# Polarshield_v2_0d.net
KiCad netlist of a schematic drawn in EAGLE
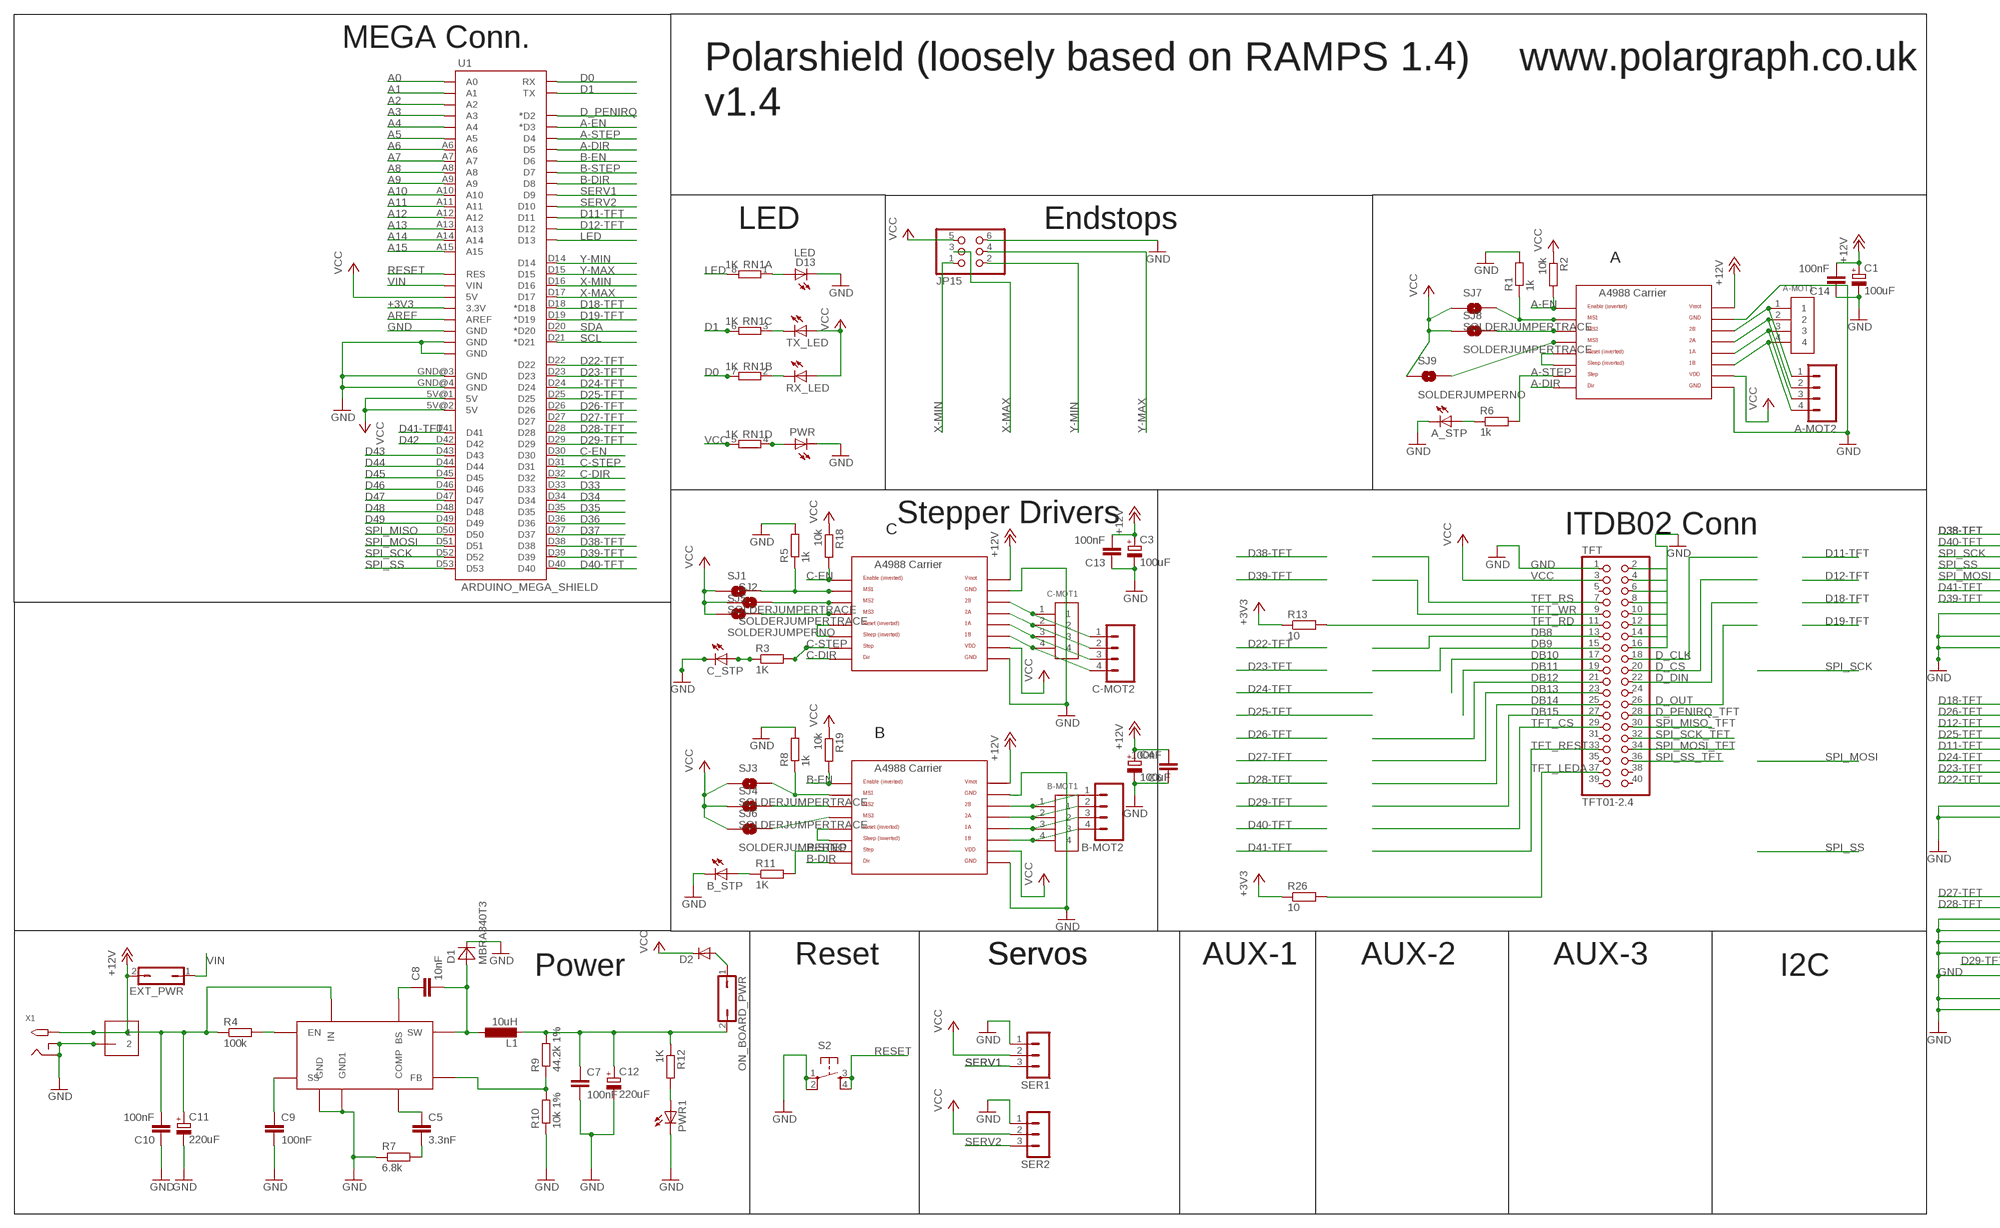
[diagram p0: schematic, sheet 1, part 1 of 2]
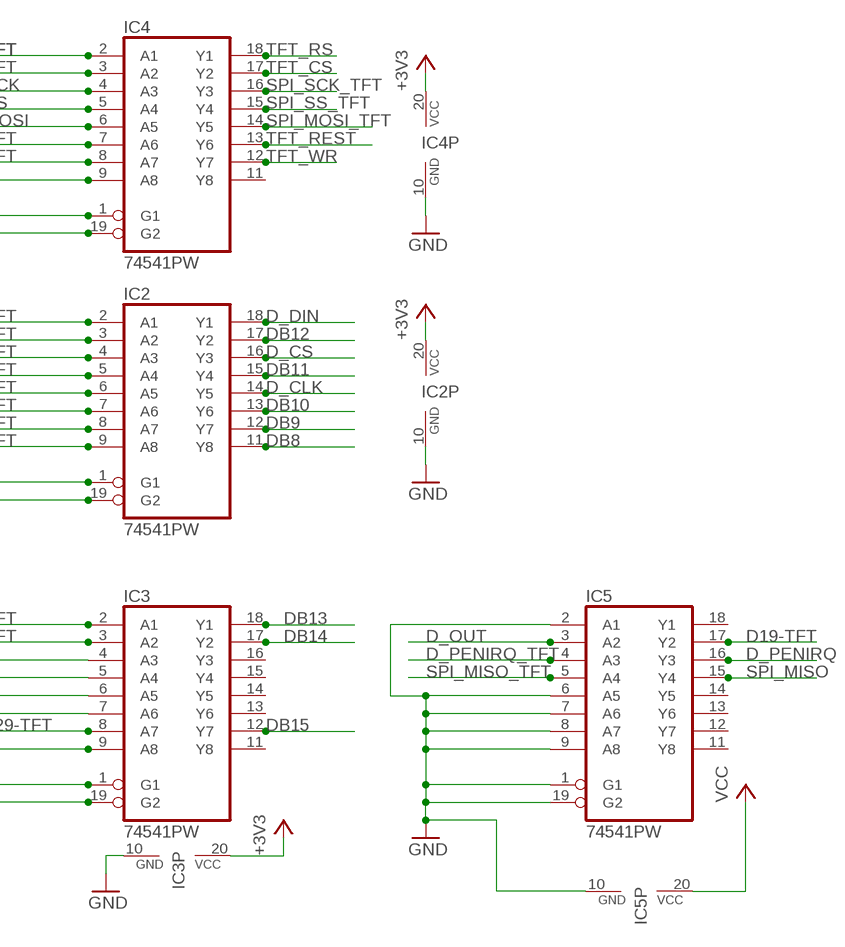
[diagram p1: schematic, sheet 1, part 2 of 2]

(export (version "E")
  (design (tool "Eeschema 10.0.6"))
  (components
    (comp (ref "A-MOT1")
      (value "1X4-BIG")
      (footprint "eagle-import:1X04-BIG")
      (libsource (lib "eagle-import") (part "1X4-BIG"))
    )
    (comp (ref "A-MOT2")
      (value "M04SCREW")
      (footprint "eagle-import:SCREWTERMINAL-3.5MM-4")
      (libsource (lib "eagle-import") (part "M04SCREW"))
    )
    (comp (ref "A_STP")
      (value "LEDCHIP-LED0805")
      (footprint "eagle-import:CHIP-LED0805")
      (libsource (lib "eagle-import") (part "LEDCHIP-LED0805"))
    )
    (comp (ref "B-MOT1")
      (value "1X4-BIG")
      (footprint "eagle-import:1X04-BIG")
      (libsource (lib "eagle-import") (part "1X4-BIG"))
    )
    (comp (ref "B-MOT2")
      (value "M04SCREW")
      (footprint "eagle-import:SCREWTERMINAL-3.5MM-4")
      (libsource (lib "eagle-import") (part "M04SCREW"))
    )
    (comp (ref "B_STP")
      (value "LEDCHIP-LED0805")
      (footprint "eagle-import:CHIP-LED0805")
      (libsource (lib "eagle-import") (part "LEDCHIP-LED0805"))
    )
    (comp (ref "C-MOT1")
      (value "1X4-BIG")
      (footprint "eagle-import:1X04-BIG")
      (libsource (lib "eagle-import") (part "1X4-BIG"))
    )
    (comp (ref "C-MOT2")
      (value "M04SCREW")
      (footprint "eagle-import:SCREWTERMINAL-3.5MM-4")
      (libsource (lib "eagle-import") (part "M04SCREW"))
    )
    (comp (ref "C1")
      (value "100uF")
      (footprint "eagle-import:153CLV-0605")
      (libsource (lib "eagle-import") (part "CPOL-EU153CLV-0605"))
    )
    (comp (ref "C3")
      (value "100uF")
      (footprint "eagle-import:153CLV-0605")
      (libsource (lib "eagle-import") (part "CPOL-EU153CLV-0605"))
    )
    (comp (ref "C4")
      (value "100uF")
      (footprint "eagle-import:153CLV-0605")
      (libsource (lib "eagle-import") (part "CPOL-EU153CLV-0605"))
    )
    (comp (ref "C5")
      (value "3.3nF")
      (footprint "eagle-import:C0805K")
      (libsource (lib "eagle-import") (part "C-EUC0805K"))
    )
    (comp (ref "C6")
      (value "100nF")
      (footprint "eagle-import:C0805")
      (libsource (lib "eagle-import") (part "C-EUC0805"))
    )
    (comp (ref "C7")
      (value "100nF")
      (footprint "eagle-import:C0805K")
      (libsource (lib "eagle-import") (part "C-EUC0805K"))
    )
    (comp (ref "C8")
      (value "10nF")
      (footprint "eagle-import:C0805K")
      (libsource (lib "eagle-import") (part "C-EUC0805K"))
    )
    (comp (ref "C9")
      (value "100nF")
      (footprint "eagle-import:C0805K")
      (libsource (lib "eagle-import") (part "C-EUC0805K"))
    )
    (comp (ref "C10")
      (value "100nF")
      (footprint "eagle-import:C0805K")
      (libsource (lib "eagle-import") (part "C-EUC0805K"))
    )
    (comp (ref "C11")
      (value "220uF")
      (footprint "eagle-import:153CLV-0807")
      (libsource (lib "eagle-import") (part "resistor_CPOL-EU153CLV-0807"))
    )
    (comp (ref "C12")
      (value "220uF")
      (footprint "eagle-import:153CLV-0807")
      (libsource (lib "eagle-import") (part "resistor_CPOL-EU153CLV-0807"))
    )
    (comp (ref "C13")
      (value "100nF")
      (footprint "eagle-import:C0805")
      (libsource (lib "eagle-import") (part "C-EUC0805"))
    )
    (comp (ref "C14")
      (value "100nF")
      (footprint "eagle-import:C0805")
      (libsource (lib "eagle-import") (part "C-EUC0805"))
    )
    (comp (ref "C_STP")
      (value "LEDCHIP-LED0805")
      (footprint "eagle-import:CHIP-LED0805")
      (libsource (lib "eagle-import") (part "LEDCHIP-LED0805"))
    )
    (comp (ref "D1")
      (value "MBRA340T3")
      (footprint "eagle-import:SMA")
      (libsource (lib "eagle-import") (part "MBRA340T3"))
    )
    (comp (ref "D2")
      (value "DIODE-DO214BA")
      (footprint "eagle-import:DO214BA")
      (libsource (lib "eagle-import") (part "DIODE-DO214BA"))
    )
    (comp (ref "D13")
      (value "LED")
      (footprint "eagle-import:CHIP-LED0805")
      (libsource (lib "eagle-import") (part "LEDCHIP-LED0805"))
    )
    (comp (ref "EXT_PWR")
      (value "JP1Q")
      (footprint "eagle-import:JP1")
      (libsource (lib "eagle-import") (part "JP1Q"))
    )
    (comp (ref "IC1")
      (value "MP2307")
      (footprint "eagle-import:SOIC8")
      (libsource (lib "eagle-import") (part "MP2307"))
    )
    (comp (ref "IC2")
      (value "74541PW")
      (footprint "eagle-import:TSSOP20")
      (libsource (lib "eagle-import") (part "74541PW"))
    )
    (comp (ref "IC3")
      (value "74541PW")
      (footprint "eagle-import:TSSOP20")
      (libsource (lib "eagle-import") (part "74541PW"))
    )
    (comp (ref "IC4")
      (value "74541PW")
      (footprint "eagle-import:TSSOP20")
      (libsource (lib "eagle-import") (part "74541PW"))
    )
    (comp (ref "IC5")
      (value "74541PW")
      (footprint "eagle-import:TSSOP20")
      (libsource (lib "eagle-import") (part "74541PW"))
    )
    (comp (ref "J1")
      (value "1X2-3.5MM")
      (footprint "eagle-import:1X2-3.5MM")
      (libsource (lib "eagle-import") (part "1X2-3.5MM"))
    )
    (comp (ref "JP15")
      (value "PINHD-2X3")
      (footprint "eagle-import:2X03")
      (libsource (lib "eagle-import") (part "PINHD-2X3"))
    )
    (comp (ref "L1")
      (value "10uH")
      (footprint "eagle-import:PIS2816")
      (libsource (lib "eagle-import") (part "L-EUPIS2816"))
    )
    (comp (ref "ON_BOARD_PWR")
      (value "JP1Q")
      (footprint "eagle-import:JP1")
      (libsource (lib "eagle-import") (part "JP1Q"))
    )
    (comp (ref "PWR")
      (value "LEDCHIP-LED0805")
      (footprint "eagle-import:CHIP-LED0805")
      (libsource (lib "eagle-import") (part "LEDCHIP-LED0805"))
    )
    (comp (ref "PWR1")
      (value "LEDCHIP-LED0805")
      (footprint "eagle-import:CHIP-LED0805")
      (libsource (lib "eagle-import") (part "LEDCHIP-LED0805"))
    )
    (comp (ref "R1")
      (value "1k")
      (footprint "eagle-import:R0805")
      (libsource (lib "eagle-import") (part "R-EU_R0805"))
    )
    (comp (ref "R2")
      (value "10k")
      (footprint "eagle-import:R0805")
      (libsource (lib "eagle-import") (part "R-EU_R0805"))
    )
    (comp (ref "R3")
      (value "1K")
      (footprint "eagle-import:R0805")
      (libsource (lib "eagle-import") (part "R-EU_R0805"))
    )
    (comp (ref "R4")
      (value "100k")
      (footprint "eagle-import:R0805")
      (libsource (lib "eagle-import") (part "resistor_R-EU_R0805"))
    )
    (comp (ref "R5")
      (value "1k")
      (footprint "eagle-import:R0805")
      (libsource (lib "eagle-import") (part "R-EU_R0805"))
    )
    (comp (ref "R6")
      (value "1k")
      (footprint "eagle-import:R0805")
      (libsource (lib "eagle-import") (part "R-EU_R0805"))
    )
    (comp (ref "R7")
      (value "6.8k")
      (footprint "eagle-import:R0805")
      (libsource (lib "eagle-import") (part "resistor_R-EU_R0805"))
    )
    (comp (ref "R8")
      (value "1k")
      (footprint "eagle-import:R0805")
      (libsource (lib "eagle-import") (part "R-EU_R0805"))
    )
    (comp (ref "R9")
      (value "44.2k 1%")
      (footprint "eagle-import:R0805")
      (libsource (lib "eagle-import") (part "resistor_R-EU_R0805"))
    )
    (comp (ref "R10")
      (value "10k 1%")
      (footprint "eagle-import:R0805")
      (libsource (lib "eagle-import") (part "resistor_R-EU_R0805"))
    )
    (comp (ref "R11")
      (value "1K")
      (footprint "eagle-import:R0805")
      (libsource (lib "eagle-import") (part "R-EU_R0805"))
    )
    (comp (ref "R12")
      (value "1K")
      (footprint "eagle-import:R0805")
      (libsource (lib "eagle-import") (part "R-EU_R0805"))
    )
    (comp (ref "R13")
      (value "10")
      (footprint "eagle-import:R0805")
      (libsource (lib "eagle-import") (part "resistor_R-EU_R0805"))
    )
    (comp (ref "R18")
      (value "10k")
      (footprint "eagle-import:R0805")
      (libsource (lib "eagle-import") (part "R-EU_R0805"))
    )
    (comp (ref "R19")
      (value "10k")
      (footprint "eagle-import:R0805")
      (libsource (lib "eagle-import") (part "R-EU_R0805"))
    )
    (comp (ref "R26")
      (value "10")
      (footprint "eagle-import:R0805")
      (libsource (lib "eagle-import") (part "resistor_R-EU_R0805"))
    )
    (comp (ref "RN1")
      (value "1K")
      (footprint "eagle-import:EXBS8V")
      (libsource (lib "eagle-import") (part "4R-NEXBS8V"))
    )
    (comp (ref "RX_LED")
      (value "LEDCHIP-LED0805")
      (footprint "eagle-import:CHIP-LED0805")
      (libsource (lib "eagle-import") (part "LEDCHIP-LED0805"))
    )
    (comp (ref "S2")
      (value "TAC_SWITCHPTH")
      (footprint "eagle-import:TACTILE-PTH")
      (libsource (lib "eagle-import") (part "TAC_SWITCHPTH"))
    )
    (comp (ref "SER1")
      (value "3PIN-HEADER")
      (footprint "eagle-import:3PIN-HEADER")
      (libsource (lib "eagle-import") (part "3PIN-HEADER"))
    )
    (comp (ref "SER2")
      (value "3PIN-HEADER")
      (footprint "eagle-import:3PIN-HEADER")
      (libsource (lib "eagle-import") (part "3PIN-HEADER"))
    )
    (comp (ref "SJ1")
      (value "SOLDERJUMPERTRACE")
      (footprint "eagle-import:SJ_2S-TRACE")
      (libsource (lib "eagle-import") (part "SOLDERJUMPERTRACE"))
    )
    (comp (ref "SJ2")
      (value "SOLDERJUMPERTRACE")
      (footprint "eagle-import:SJ_2S-TRACE")
      (libsource (lib "eagle-import") (part "SOLDERJUMPERTRACE"))
    )
    (comp (ref "SJ3")
      (value "SOLDERJUMPERTRACE")
      (footprint "eagle-import:SJ_2S-TRACE")
      (libsource (lib "eagle-import") (part "SOLDERJUMPERTRACE"))
    )
    (comp (ref "SJ4")
      (value "SOLDERJUMPERTRACE")
      (footprint "eagle-import:SJ_2S-TRACE")
      (libsource (lib "eagle-import") (part "SOLDERJUMPERTRACE"))
    )
    (comp (ref "SJ5")
      (value "SOLDERJUMPERNO")
      (footprint "eagle-import:SJ_2S-NO")
      (libsource (lib "eagle-import") (part "SOLDERJUMPERNO"))
    )
    (comp (ref "SJ6")
      (value "SOLDERJUMPERNO")
      (footprint "eagle-import:SJ_2S-NO")
      (libsource (lib "eagle-import") (part "SOLDERJUMPERNO"))
    )
    (comp (ref "SJ7")
      (value "SOLDERJUMPERTRACE")
      (footprint "eagle-import:SJ_2S-TRACE")
      (libsource (lib "eagle-import") (part "SOLDERJUMPERTRACE"))
    )
    (comp (ref "SJ8")
      (value "SOLDERJUMPERTRACE")
      (footprint "eagle-import:SJ_2S-TRACE")
      (libsource (lib "eagle-import") (part "SOLDERJUMPERTRACE"))
    )
    (comp (ref "SJ9")
      (value "SOLDERJUMPERNO")
      (footprint "eagle-import:SJ_2S-NO")
      (libsource (lib "eagle-import") (part "SOLDERJUMPERNO"))
    )
    (comp (ref "TFT")
      (value "TFT01-2.4")
      (footprint "eagle-import:TFT01-2.4")
      (libsource (lib "eagle-import") (part "TFT01-2.4"))
    )
    (comp (ref "TX_LED")
      (value "LEDCHIP-LED0805")
      (footprint "eagle-import:CHIP-LED0805")
      (libsource (lib "eagle-import") (part "LEDCHIP-LED0805"))
    )
    (comp (ref "U$1")
      (value "A4988BREAKOUT")
      (footprint "eagle-import:A4988BREAKOUT")
      (libsource (lib "eagle-import") (part "A4988BREAKOUT"))
    )
    (comp (ref "U$6")
      (value "A4988BREAKOUT")
      (footprint "eagle-import:A4988BREAKOUT")
      (libsource (lib "eagle-import") (part "A4988BREAKOUT"))
    )
    (comp (ref "U$7")
      (value "A4988BREAKOUT")
      (footprint "eagle-import:A4988BREAKOUT")
      (libsource (lib "eagle-import") (part "A4988BREAKOUT"))
    )
    (comp (ref "U1")
      (value "ARDUINO_MEGA_SHIELD")
      (footprint "eagle-import:ARDUINO_MEGA_SHIELD")
      (libsource (lib "eagle-import") (part "ARDUINO_MEGA_SHIELD"))
    )
    (comp (ref "X1")
      (value "2.1MMJACKTHM")
      (footprint "eagle-import:PJ-102A")
      (libsource (lib "eagle-import") (part "2.1MMJACKTHM"))
    )
  )
  (nets
    (net (code "1") (name "+3V3") (class "Default")
      (node (ref "IC2") (pin "20") (pinfunction "VCC_20") (pintype "power_in"))
      (node (ref "IC3") (pin "20") (pinfunction "VCC_20") (pintype "power_in"))
      (node (ref "IC4") (pin "20") (pinfunction "VCC_20") (pintype "power_in"))
      (node (ref "R13") (pin "1") (pinfunction "1_1") (pintype "passive"))
      (node (ref "R26") (pin "1") (pinfunction "1_1") (pintype "passive"))
      (node (ref "U1") (pin "3.3V") (pinfunction "3.3V_3.3V") (pintype "bidirectional"))
    )
    (net (code "2") (name "+12V") (class "Default")
      (node (ref "C1") (pin "+") (pinfunction "+_+") (pintype "passive"))
      (node (ref "C10") (pin "2") (pinfunction "2_2") (pintype "passive"))
      (node (ref "C11") (pin "+") (pinfunction "+_+") (pintype "passive"))
      (node (ref "C13") (pin "2") (pinfunction "2_2") (pintype "passive"))
      (node (ref "C14") (pin "2") (pinfunction "2_2") (pintype "passive"))
      (node (ref "C3") (pin "+") (pinfunction "+_+") (pintype "passive"))
      (node (ref "C4") (pin "+") (pinfunction "+_+") (pintype "passive"))
      (node (ref "C6") (pin "2") (pinfunction "2_2") (pintype "passive"))
      (node (ref "EXT_PWR") (pin "2") (pinfunction "2_2") (pintype "passive"))
      (node (ref "IC1") (pin "IN") (pinfunction "IN_IN") (pintype "bidirectional"))
      (node (ref "J1") (pin "1") (pinfunction "1_1") (pintype "passive"))
      (node (ref "R4") (pin "1") (pinfunction "1_1") (pintype "passive"))
      (node (ref "U$1") (pin "VMOT") (pinfunction "VMOT_VMOT") (pintype "power_in"))
      (node (ref "U$6") (pin "VMOT") (pinfunction "VMOT_VMOT") (pintype "power_in"))
      (node (ref "U$7") (pin "VMOT") (pinfunction "VMOT_VMOT") (pintype "power_in"))
      (node (ref "X1") (pin "TIP") (pinfunction "TIP_TIP") (pintype "bidirectional"))
    )
    (net (code "3") (name "/A-DIR") (class "Default")
      (node (ref "U$1") (pin "DIR") (pinfunction "DIR_DIR") (pintype "input"))
      (node (ref "U1") (pin "D5") (pinfunction "D5_D5") (pintype "bidirectional"))
    )
    (net (code "4") (name "/A-EN") (class "Default")
      (node (ref "R2") (pin "2") (pinfunction "2_2") (pintype "passive"))
      (node (ref "U$1") (pin "EN") (pinfunction "EN_EN") (pintype "input"))
      (node (ref "U1") (pin "D3") (pinfunction "*D3_D3") (pintype "bidirectional"))
    )
    (net (code "5") (name "/A-STEP") (class "Default")
      (node (ref "R6") (pin "2") (pinfunction "2_2") (pintype "passive"))
      (node (ref "U$1") (pin "STEP") (pinfunction "STEP_STEP") (pintype "input"))
      (node (ref "U1") (pin "D4") (pinfunction "D4_D4") (pintype "bidirectional"))
    )
    (net (code "6") (name "/A0") (class "Default")
      (node (ref "U1") (pin "A0") (pinfunction "A0_A0") (pintype "bidirectional"))
    )
    (net (code "7") (name "/A1") (class "Default")
      (node (ref "U1") (pin "A1") (pinfunction "A1_A1") (pintype "bidirectional"))
    )
    (net (code "8") (name "/A2") (class "Default")
      (node (ref "U1") (pin "A2") (pinfunction "A2_A2") (pintype "bidirectional"))
    )
    (net (code "9") (name "/A3") (class "Default")
      (node (ref "U1") (pin "A3") (pinfunction "A3_A3") (pintype "bidirectional"))
    )
    (net (code "10") (name "/A4") (class "Default")
      (node (ref "U1") (pin "A4") (pinfunction "A4_A4") (pintype "bidirectional"))
    )
    (net (code "11") (name "/A5") (class "Default")
      (node (ref "U1") (pin "A5") (pinfunction "A5_A5") (pintype "bidirectional"))
    )
    (net (code "12") (name "/A6") (class "Default")
      (node (ref "U1") (pin "A6") (pinfunction "A6_A6") (pintype "bidirectional"))
    )
    (net (code "13") (name "/A7") (class "Default")
      (node (ref "U1") (pin "A7") (pinfunction "A7_A7") (pintype "bidirectional"))
    )
    (net (code "14") (name "/A8") (class "Default")
      (node (ref "U1") (pin "A8") (pinfunction "A8_A8") (pintype "bidirectional"))
    )
    (net (code "15") (name "/A9") (class "Default")
      (node (ref "U1") (pin "A9") (pinfunction "A9_A9") (pintype "bidirectional"))
    )
    (net (code "16") (name "/A10") (class "Default")
      (node (ref "U1") (pin "A10") (pinfunction "A10_A10") (pintype "bidirectional"))
    )
    (net (code "17") (name "/A11") (class "Default")
      (node (ref "U1") (pin "A11") (pinfunction "A11_A11") (pintype "bidirectional"))
    )
    (net (code "18") (name "/A12") (class "Default")
      (node (ref "U1") (pin "A12") (pinfunction "A12_A12") (pintype "bidirectional"))
    )
    (net (code "19") (name "/A13") (class "Default")
      (node (ref "U1") (pin "A13") (pinfunction "A13_A13") (pintype "bidirectional"))
    )
    (net (code "20") (name "/A14") (class "Default")
      (node (ref "U1") (pin "A14") (pinfunction "A14_A14") (pintype "bidirectional"))
    )
    (net (code "21") (name "/A15") (class "Default")
      (node (ref "U1") (pin "A15") (pinfunction "A15_A15") (pintype "bidirectional"))
    )
    (net (code "22") (name "/AREF") (class "Default")
      (node (ref "U1") (pin "AREF") (pinfunction "AREF_AREF") (pintype "bidirectional"))
    )
    (net (code "23") (name "/B-DIR") (class "Default")
      (node (ref "U$7") (pin "DIR") (pinfunction "DIR_DIR") (pintype "input"))
      (node (ref "U1") (pin "D8") (pinfunction "D8_D8") (pintype "bidirectional"))
    )
    (net (code "24") (name "/B-EN") (class "Default")
      (node (ref "R19") (pin "2") (pinfunction "2_2") (pintype "passive"))
      (node (ref "U$7") (pin "EN") (pinfunction "EN_EN") (pintype "input"))
      (node (ref "U1") (pin "D6") (pinfunction "D6_D6") (pintype "bidirectional"))
    )
    (net (code "25") (name "/B-STEP") (class "Default")
      (node (ref "R11") (pin "2") (pinfunction "2_2") (pintype "passive"))
      (node (ref "U$7") (pin "STEP") (pinfunction "STEP_STEP") (pintype "input"))
      (node (ref "U1") (pin "D7") (pinfunction "D7_D7") (pintype "bidirectional"))
    )
    (net (code "26") (name "/C-DIR") (class "Default")
      (node (ref "U$6") (pin "DIR") (pinfunction "DIR_DIR") (pintype "input"))
      (node (ref "U1") (pin "D32") (pinfunction "D32_D32") (pintype "bidirectional"))
    )
    (net (code "27") (name "/C-EN") (class "Default")
      (node (ref "R18") (pin "2") (pinfunction "2_2") (pintype "passive"))
      (node (ref "U$6") (pin "EN") (pinfunction "EN_EN") (pintype "input"))
      (node (ref "U1") (pin "D30") (pinfunction "D30_D30") (pintype "bidirectional"))
    )
    (net (code "28") (name "/C-STEP") (class "Default")
      (node (ref "R3") (pin "2") (pinfunction "2_2") (pintype "passive"))
      (node (ref "U$6") (pin "STEP") (pinfunction "STEP_STEP") (pintype "input"))
      (node (ref "U1") (pin "D31") (pinfunction "D31_D31") (pintype "bidirectional"))
    )
    (net (code "29") (name "/D0") (class "Default")
      (node (ref "RN1") (pin "7") (pinfunction "2_7") (pintype "passive"))
      (node (ref "U1") (pin "RX") (pinfunction "RX_RX") (pintype "bidirectional"))
    )
    (net (code "30") (name "/D1") (class "Default")
      (node (ref "RN1") (pin "6") (pinfunction "2_6") (pintype "passive"))
      (node (ref "U1") (pin "TX") (pinfunction "TX_TX") (pintype "bidirectional"))
    )
    (net (code "31") (name "/D11-TFT") (class "Default")
      (node (ref "IC2") (pin "6") (pinfunction "A5_6") (pintype "input"))
      (node (ref "U1") (pin "D11") (pinfunction "D11_D11") (pintype "bidirectional"))
    )
    (net (code "32") (name "/D12-TFT") (class "Default")
      (node (ref "IC2") (pin "4") (pinfunction "A3_4") (pintype "input"))
      (node (ref "U1") (pin "D12") (pinfunction "D12_D12") (pintype "bidirectional"))
    )
    (net (code "33") (name "/D18-TFT") (class "Default")
      (node (ref "IC2") (pin "2") (pinfunction "A1_2") (pintype "input"))
      (node (ref "U1") (pin "D18") (pinfunction "*D18_D18") (pintype "bidirectional"))
    )
    (net (code "34") (name "/D19-TFT") (class "Default")
      (node (ref "IC5") (pin "17") (pinfunction "Y2_17") (pintype "tri_state"))
      (node (ref "U1") (pin "D19") (pinfunction "*D19_D19") (pintype "bidirectional"))
    )
    (net (code "35") (name "/D22-TFT") (class "Default")
      (node (ref "IC2") (pin "9") (pinfunction "A8_9") (pintype "input"))
      (node (ref "U1") (pin "D22") (pinfunction "D22_D22") (pintype "bidirectional"))
    )
    (net (code "36") (name "/D23-TFT") (class "Default")
      (node (ref "IC2") (pin "8") (pinfunction "A7_8") (pintype "input"))
      (node (ref "U1") (pin "D23") (pinfunction "D23_D23") (pintype "bidirectional"))
    )
    (net (code "37") (name "/D24-TFT") (class "Default")
      (node (ref "IC2") (pin "7") (pinfunction "A6_7") (pintype "input"))
      (node (ref "U1") (pin "D24") (pinfunction "D24_D24") (pintype "bidirectional"))
    )
    (net (code "38") (name "/D25-TFT") (class "Default")
      (node (ref "IC2") (pin "5") (pinfunction "A4_5") (pintype "input"))
      (node (ref "U1") (pin "D25") (pinfunction "D25_D25") (pintype "bidirectional"))
    )
    (net (code "39") (name "/D26-TFT") (class "Default")
      (node (ref "IC2") (pin "3") (pinfunction "A2_3") (pintype "input"))
      (node (ref "U1") (pin "D26") (pinfunction "D26_D26") (pintype "bidirectional"))
    )
    (net (code "40") (name "/D27-TFT") (class "Default")
      (node (ref "IC3") (pin "2") (pinfunction "A1_2") (pintype "input"))
      (node (ref "U1") (pin "D27") (pinfunction "D27_D27") (pintype "bidirectional"))
    )
    (net (code "41") (name "/D28-TFT") (class "Default")
      (node (ref "IC3") (pin "3") (pinfunction "A2_3") (pintype "input"))
      (node (ref "U1") (pin "D28") (pinfunction "D28_D28") (pintype "bidirectional"))
    )
    (net (code "42") (name "/D29-TFT") (class "Default")
      (node (ref "IC3") (pin "8") (pinfunction "A7_8") (pintype "input"))
      (node (ref "U1") (pin "D29") (pinfunction "D29_D29") (pintype "bidirectional"))
    )
    (net (code "43") (name "/D33") (class "Default")
      (node (ref "U1") (pin "D33") (pinfunction "D33_D33") (pintype "bidirectional"))
    )
    (net (code "44") (name "/D34") (class "Default")
      (node (ref "U1") (pin "D34") (pinfunction "D34_D34") (pintype "bidirectional"))
    )
    (net (code "45") (name "/D35") (class "Default")
      (node (ref "U1") (pin "D35") (pinfunction "D35_D35") (pintype "bidirectional"))
    )
    (net (code "46") (name "/D36") (class "Default")
      (node (ref "U1") (pin "D36") (pinfunction "D36_D36") (pintype "bidirectional"))
    )
    (net (code "47") (name "/D37") (class "Default")
      (node (ref "U1") (pin "D37") (pinfunction "D37_D37") (pintype "bidirectional"))
    )
    (net (code "48") (name "/D38-TFT") (class "Default")
      (node (ref "IC4") (pin "2") (pinfunction "A1_2") (pintype "input"))
      (node (ref "U1") (pin "D38") (pinfunction "D38_D38") (pintype "bidirectional"))
    )
    (net (code "49") (name "/D39-TFT") (class "Default")
      (node (ref "IC4") (pin "8") (pinfunction "A7_8") (pintype "input"))
      (node (ref "U1") (pin "D39") (pinfunction "D39_D39") (pintype "bidirectional"))
    )
    (net (code "50") (name "/D40-TFT") (class "Default")
      (node (ref "IC4") (pin "3") (pinfunction "A2_3") (pintype "input"))
      (node (ref "U1") (pin "D40") (pinfunction "D40_D40") (pintype "bidirectional"))
    )
    (net (code "51") (name "/D41-TFT") (class "Default")
      (node (ref "IC4") (pin "7") (pinfunction "A6_7") (pintype "input"))
      (node (ref "U1") (pin "D41") (pinfunction "D41_D41") (pintype "bidirectional"))
    )
    (net (code "52") (name "/D42") (class "Default")
      (node (ref "U1") (pin "D42") (pinfunction "D42_D42") (pintype "bidirectional"))
    )
    (net (code "53") (name "/D43") (class "Default")
      (node (ref "U1") (pin "D43") (pinfunction "D43_D43") (pintype "bidirectional"))
    )
    (net (code "54") (name "/D44") (class "Default")
      (node (ref "U1") (pin "D44") (pinfunction "D44_D44") (pintype "bidirectional"))
    )
    (net (code "55") (name "/D45") (class "Default")
      (node (ref "U1") (pin "D45") (pinfunction "D45_D45") (pintype "bidirectional"))
    )
    (net (code "56") (name "/D46") (class "Default")
      (node (ref "U1") (pin "D46") (pinfunction "D46_D46") (pintype "bidirectional"))
    )
    (net (code "57") (name "/D47") (class "Default")
      (node (ref "U1") (pin "D47") (pinfunction "D47_D47") (pintype "bidirectional"))
    )
    (net (code "58") (name "/D48") (class "Default")
      (node (ref "U1") (pin "D48") (pinfunction "D48_D48") (pintype "bidirectional"))
    )
    (net (code "59") (name "/D49") (class "Default")
      (node (ref "U1") (pin "D49") (pinfunction "D49_D49") (pintype "bidirectional"))
    )
    (net (code "60") (name "/DB8") (class "Default")
      (node (ref "IC2") (pin "11") (pinfunction "Y8_11") (pintype "tri_state"))
      (node (ref "TFT") (pin "13") (pinfunction "13_13") (pintype "passive"))
    )
    (net (code "61") (name "/DB9") (class "Default")
      (node (ref "IC2") (pin "12") (pinfunction "Y7_12") (pintype "tri_state"))
      (node (ref "TFT") (pin "15") (pinfunction "15_15") (pintype "passive"))
    )
    (net (code "62") (name "/DB10") (class "Default")
      (node (ref "IC2") (pin "13") (pinfunction "Y6_13") (pintype "tri_state"))
      (node (ref "TFT") (pin "17") (pinfunction "17_17") (pintype "passive"))
    )
    (net (code "63") (name "/DB11") (class "Default")
      (node (ref "IC2") (pin "15") (pinfunction "Y4_15") (pintype "tri_state"))
      (node (ref "TFT") (pin "19") (pinfunction "19_19") (pintype "passive"))
    )
    (net (code "64") (name "/DB12") (class "Default")
      (node (ref "IC2") (pin "17") (pinfunction "Y2_17") (pintype "tri_state"))
      (node (ref "TFT") (pin "21") (pinfunction "21_21") (pintype "passive"))
    )
    (net (code "65") (name "/DB13") (class "Default")
      (node (ref "IC3") (pin "18") (pinfunction "Y1_18") (pintype "tri_state"))
      (node (ref "TFT") (pin "23") (pinfunction "23_23") (pintype "passive"))
    )
    (net (code "66") (name "/DB14") (class "Default")
      (node (ref "IC3") (pin "17") (pinfunction "Y2_17") (pintype "tri_state"))
      (node (ref "TFT") (pin "25") (pinfunction "25_25") (pintype "passive"))
    )
    (net (code "67") (name "/DB15") (class "Default")
      (node (ref "IC3") (pin "12") (pinfunction "Y7_12") (pintype "tri_state"))
      (node (ref "TFT") (pin "27") (pinfunction "27_27") (pintype "passive"))
    )
    (net (code "68") (name "/D_CLK") (class "Default")
      (node (ref "IC2") (pin "14") (pinfunction "Y5_14") (pintype "tri_state"))
      (node (ref "TFT") (pin "18") (pinfunction "18_18") (pintype "passive"))
    )
    (net (code "69") (name "/D_CS") (class "Default")
      (node (ref "IC2") (pin "16") (pinfunction "Y3_16") (pintype "tri_state"))
      (node (ref "TFT") (pin "20") (pinfunction "20_20") (pintype "passive"))
    )
    (net (code "70") (name "/D_DIN") (class "Default")
      (node (ref "IC2") (pin "18") (pinfunction "Y1_18") (pintype "tri_state"))
      (node (ref "TFT") (pin "22") (pinfunction "22_22") (pintype "passive"))
    )
    (net (code "71") (name "/D_OUT") (class "Default")
      (node (ref "IC5") (pin "3") (pinfunction "A2_3") (pintype "input"))
      (node (ref "TFT") (pin "26") (pinfunction "26_26") (pintype "passive"))
    )
    (net (code "72") (name "/D_PENIRQ") (class "Default")
      (node (ref "IC5") (pin "16") (pinfunction "Y3_16") (pintype "tri_state"))
      (node (ref "U1") (pin "D2") (pinfunction "*D2_D2") (pintype "bidirectional"))
    )
    (net (code "73") (name "/D_PENIRQ_TFT") (class "Default")
      (node (ref "IC5") (pin "4") (pinfunction "A3_4") (pintype "input"))
      (node (ref "TFT") (pin "28") (pinfunction "28_28") (pintype "passive"))
    )
    (net (code "74") (name "/LED") (class "Default")
      (node (ref "RN1") (pin "8") (pinfunction "2_8") (pintype "passive"))
      (node (ref "U1") (pin "D13") (pinfunction "D13_D13") (pintype "bidirectional"))
    )
    (net (code "75") (name "/RESET") (class "Default")
      (node (ref "S2") (pin "3") (pinfunction "3_3") (pintype "passive"))
      (node (ref "S2") (pin "4") (pinfunction "4_4") (pintype "passive"))
      (node (ref "U1") (pin "RES") (pinfunction "RES_RES") (pintype "bidirectional"))
    )
    (net (code "76") (name "/SCL") (class "Default")
      (node (ref "U1") (pin "D21") (pinfunction "*D21_D21") (pintype "bidirectional"))
    )
    (net (code "77") (name "/SDA") (class "Default")
      (node (ref "U1") (pin "D20") (pinfunction "*D20_D20") (pintype "bidirectional"))
    )
    (net (code "78") (name "/SERV1") (class "Default")
      (node (ref "SER1") (pin "3") (pinfunction "3_3") (pintype "passive"))
      (node (ref "U1") (pin "D9") (pinfunction "D9_D9") (pintype "bidirectional"))
    )
    (net (code "79") (name "/SERV2") (class "Default")
      (node (ref "SER2") (pin "3") (pinfunction "3_3") (pintype "passive"))
      (node (ref "U1") (pin "D10") (pinfunction "D10_D10") (pintype "bidirectional"))
    )
    (net (code "80") (name "/SPI_MISO") (class "Default")
      (node (ref "IC5") (pin "15") (pinfunction "Y4_15") (pintype "tri_state"))
      (node (ref "U1") (pin "D50") (pinfunction "D50_D50") (pintype "bidirectional"))
    )
    (net (code "81") (name "/SPI_MISO_TFT") (class "Default")
      (node (ref "IC5") (pin "5") (pinfunction "A4_5") (pintype "input"))
      (node (ref "TFT") (pin "30") (pinfunction "30_30") (pintype "passive"))
    )
    (net (code "82") (name "/SPI_MOSI") (class "Default")
      (node (ref "IC4") (pin "6") (pinfunction "A5_6") (pintype "input"))
      (node (ref "U1") (pin "D51") (pinfunction "D51_D51") (pintype "bidirectional"))
    )
    (net (code "83") (name "/SPI_MOSI_TFT") (class "Default")
      (node (ref "IC4") (pin "14") (pinfunction "Y5_14") (pintype "tri_state"))
      (node (ref "TFT") (pin "34") (pinfunction "34_34") (pintype "passive"))
    )
    (net (code "84") (name "/SPI_SCK") (class "Default")
      (node (ref "IC4") (pin "4") (pinfunction "A3_4") (pintype "input"))
      (node (ref "U1") (pin "D52") (pinfunction "D52_D52") (pintype "bidirectional"))
    )
    (net (code "85") (name "/SPI_SCK_TFT") (class "Default")
      (node (ref "IC4") (pin "16") (pinfunction "Y3_16") (pintype "tri_state"))
      (node (ref "TFT") (pin "32") (pinfunction "32_32") (pintype "passive"))
    )
    (net (code "86") (name "/SPI_SS") (class "Default")
      (node (ref "IC4") (pin "5") (pinfunction "A4_5") (pintype "input"))
      (node (ref "U1") (pin "D53") (pinfunction "D53_D53") (pintype "bidirectional"))
    )
    (net (code "87") (name "/SPI_SS_TFT") (class "Default")
      (node (ref "IC4") (pin "15") (pinfunction "Y4_15") (pintype "tri_state"))
      (node (ref "TFT") (pin "36") (pinfunction "36_36") (pintype "passive"))
    )
    (net (code "88") (name "/TFT_CS") (class "Default")
      (node (ref "IC4") (pin "17") (pinfunction "Y2_17") (pintype "tri_state"))
      (node (ref "TFT") (pin "29") (pinfunction "29_29") (pintype "passive"))
    )
    (net (code "89") (name "/TFT_LEDA") (class "Default")
      (node (ref "R26") (pin "2") (pinfunction "2_2") (pintype "passive"))
      (node (ref "TFT") (pin "37") (pinfunction "37_37") (pintype "passive"))
    )
    (net (code "90") (name "/TFT_RD") (class "Default")
      (node (ref "R13") (pin "2") (pinfunction "2_2") (pintype "passive"))
      (node (ref "TFT") (pin "11") (pinfunction "11_11") (pintype "passive"))
    )
    (net (code "91") (name "/TFT_REST") (class "Default")
      (node (ref "IC4") (pin "13") (pinfunction "Y6_13") (pintype "tri_state"))
      (node (ref "TFT") (pin "33") (pinfunction "33_33") (pintype "passive"))
    )
    (net (code "92") (name "/TFT_RS") (class "Default")
      (node (ref "IC4") (pin "18") (pinfunction "Y1_18") (pintype "tri_state"))
      (node (ref "TFT") (pin "7") (pinfunction "7_7") (pintype "passive"))
    )
    (net (code "93") (name "/TFT_WR") (class "Default")
      (node (ref "IC4") (pin "12") (pinfunction "Y7_12") (pintype "tri_state"))
      (node (ref "TFT") (pin "9") (pinfunction "9_9") (pintype "passive"))
    )
    (net (code "94") (name "/VIN") (class "Default")
      (node (ref "EXT_PWR") (pin "1") (pinfunction "1_1") (pintype "passive"))
      (node (ref "U1") (pin "VIN") (pinfunction "VIN_VIN") (pintype "bidirectional"))
    )
    (net (code "95") (name "/X-MAX") (class "Default")
      (node (ref "JP15") (pin "3") (pinfunction "3_3") (pintype "passive"))
      (node (ref "U1") (pin "D17") (pinfunction "D17_D17") (pintype "bidirectional"))
    )
    (net (code "96") (name "/X-MIN") (class "Default")
      (node (ref "JP15") (pin "1") (pinfunction "1_1") (pintype "passive"))
      (node (ref "U1") (pin "D16") (pinfunction "D16_D16") (pintype "bidirectional"))
    )
    (net (code "97") (name "/Y-MAX") (class "Default")
      (node (ref "JP15") (pin "4") (pinfunction "4_4") (pintype "passive"))
      (node (ref "U1") (pin "D15") (pinfunction "D15_D15") (pintype "bidirectional"))
    )
    (net (code "98") (name "/Y-MIN") (class "Default")
      (node (ref "JP15") (pin "2") (pinfunction "2_2") (pintype "passive"))
      (node (ref "U1") (pin "D14") (pinfunction "D14_D14") (pintype "bidirectional"))
    )
    (net (code "99") (name "GND") (class "Default")
      (node (ref "A_STP") (pin "C") (pinfunction "C_C") (pintype "passive"))
      (node (ref "B_STP") (pin "C") (pinfunction "C_C") (pintype "passive"))
      (node (ref "C1") (pin "-") (pinfunction "-_-") (pintype "passive"))
      (node (ref "C10") (pin "1") (pinfunction "1_1") (pintype "passive"))
      (node (ref "C11") (pin "-") (pinfunction "-_-") (pintype "passive"))
      (node (ref "C12") (pin "-") (pinfunction "-_-") (pintype "passive"))
      (node (ref "C13") (pin "1") (pinfunction "1_1") (pintype "passive"))
      (node (ref "C14") (pin "1") (pinfunction "1_1") (pintype "passive"))
      (node (ref "C3") (pin "-") (pinfunction "-_-") (pintype "passive"))
      (node (ref "C4") (pin "-") (pinfunction "-_-") (pintype "passive"))
      (node (ref "C6") (pin "1") (pinfunction "1_1") (pintype "passive"))
      (node (ref "C7") (pin "2") (pinfunction "2_2") (pintype "passive"))
      (node (ref "C9") (pin "2") (pinfunction "2_2") (pintype "passive"))
      (node (ref "C_STP") (pin "C") (pinfunction "C_C") (pintype "passive"))
      (node (ref "D1") (pin "C") (pinfunction "C_C") (pintype "passive"))
      (node (ref "D13") (pin "C") (pinfunction "C_C") (pintype "passive"))
      (node (ref "IC1") (pin "GND") (pinfunction "GND_GND") (pintype "bidirectional"))
      (node (ref "IC1") (pin "GND1") (pinfunction "GND1_GND1") (pintype "bidirectional"))
      (node (ref "IC2") (pin "1") (pinfunction "G1_1") (pintype "input"))
      (node (ref "IC2") (pin "10") (pinfunction "GND_10") (pintype "power_in"))
      (node (ref "IC2") (pin "19") (pinfunction "G2_19") (pintype "input"))
      (node (ref "IC3") (pin "1") (pinfunction "G1_1") (pintype "input"))
      (node (ref "IC3") (pin "10") (pinfunction "GND_10") (pintype "power_in"))
      (node (ref "IC3") (pin "19") (pinfunction "G2_19") (pintype "input"))
      (node (ref "IC3") (pin "4") (pinfunction "A3_4") (pintype "input"))
      (node (ref "IC3") (pin "5") (pinfunction "A4_5") (pintype "input"))
      (node (ref "IC3") (pin "6") (pinfunction "A5_6") (pintype "input"))
      (node (ref "IC3") (pin "7") (pinfunction "A6_7") (pintype "input"))
      (node (ref "IC3") (pin "9") (pinfunction "A8_9") (pintype "input"))
      (node (ref "IC4") (pin "1") (pinfunction "G1_1") (pintype "input"))
      (node (ref "IC4") (pin "10") (pinfunction "GND_10") (pintype "power_in"))
      (node (ref "IC4") (pin "19") (pinfunction "G2_19") (pintype "input"))
      (node (ref "IC4") (pin "9") (pinfunction "A8_9") (pintype "input"))
      (node (ref "IC5") (pin "1") (pinfunction "G1_1") (pintype "input"))
      (node (ref "IC5") (pin "10") (pinfunction "GND_10") (pintype "power_in"))
      (node (ref "IC5") (pin "19") (pinfunction "G2_19") (pintype "input"))
      (node (ref "IC5") (pin "2") (pinfunction "A1_2") (pintype "input"))
      (node (ref "IC5") (pin "6") (pinfunction "A5_6") (pintype "input"))
      (node (ref "IC5") (pin "7") (pinfunction "A6_7") (pintype "input"))
      (node (ref "IC5") (pin "8") (pinfunction "A7_8") (pintype "input"))
      (node (ref "IC5") (pin "9") (pinfunction "A8_9") (pintype "input"))
      (node (ref "J1") (pin "2") (pinfunction "2_2") (pintype "passive"))
      (node (ref "JP15") (pin "6") (pinfunction "6_6") (pintype "passive"))
      (node (ref "PWR") (pin "C") (pinfunction "C_C") (pintype "passive"))
      (node (ref "PWR1") (pin "C") (pinfunction "C_C") (pintype "passive"))
      (node (ref "R1") (pin "2") (pinfunction "2_2") (pintype "passive"))
      (node (ref "R10") (pin "1") (pinfunction "1_1") (pintype "passive"))
      (node (ref "R5") (pin "2") (pinfunction "2_2") (pintype "passive"))
      (node (ref "R7") (pin "1") (pinfunction "1_1") (pintype "passive"))
      (node (ref "R8") (pin "2") (pinfunction "2_2") (pintype "passive"))
      (node (ref "S2") (pin "1") (pinfunction "1_1") (pintype "passive"))
      (node (ref "S2") (pin "2") (pinfunction "2_2") (pintype "passive"))
      (node (ref "SER1") (pin "1") (pinfunction "1_1") (pintype "passive"))
      (node (ref "SER2") (pin "1") (pinfunction "1_1") (pintype "passive"))
      (node (ref "TFT") (pin "1") (pinfunction "1_1") (pintype "passive"))
      (node (ref "TFT") (pin "10") (pinfunction "10_10") (pintype "passive"))
      (node (ref "TFT") (pin "12") (pinfunction "12_12") (pintype "passive"))
      (node (ref "TFT") (pin "14") (pinfunction "14_14") (pintype "passive"))
      (node (ref "TFT") (pin "16") (pinfunction "16_16") (pintype "passive"))
      (node (ref "TFT") (pin "2") (pinfunction "2_2") (pintype "passive"))
      (node (ref "TFT") (pin "4") (pinfunction "4_4") (pintype "passive"))
      (node (ref "TFT") (pin "6") (pinfunction "6_6") (pintype "passive"))
      (node (ref "TFT") (pin "8") (pinfunction "8_8") (pintype "passive"))
      (node (ref "U$1") (pin "GND") (pinfunction "GND_GND") (pintype "power_in"))
      (node (ref "U$1") (pin "GND@0") (pinfunction "GND_GND@0") (pintype "power_in"))
      (node (ref "U$6") (pin "GND") (pinfunction "GND_GND") (pintype "power_in"))
      (node (ref "U$6") (pin "GND@0") (pinfunction "GND_GND@0") (pintype "power_in"))
      (node (ref "U$7") (pin "GND") (pinfunction "GND_GND") (pintype "power_in"))
      (node (ref "U$7") (pin "GND@0") (pinfunction "GND_GND@0") (pintype "power_in"))
      (node (ref "U1") (pin "GND@0") (pinfunction "GND_GND@0") (pintype "power_in"))
      (node (ref "U1") (pin "GND@1") (pinfunction "GND_GND@1") (pintype "power_in"))
      (node (ref "U1") (pin "GND@2") (pinfunction "GND_GND@2") (pintype "power_in"))
      (node (ref "U1") (pin "GND@3") (pinfunction "GND_GND@3") (pintype "power_in"))
      (node (ref "U1") (pin "GND@4") (pinfunction "GND_GND@4") (pintype "power_in"))
      (node (ref "X1") (pin "RING") (pinfunction "RING_RING") (pintype "bidirectional"))
      (node (ref "X1") (pin "RING_SW") (pinfunction "RING_SW_RING_SW") (pintype "bidirectional"))
    )
    (net (code "100") (name "Net-(A-MOT1-Pad1)") (class "Default")
      (node (ref "A-MOT1") (pin "1") (pinfunction "1_1") (pintype "bidirectional"))
      (node (ref "A-MOT2") (pin "1") (pinfunction "1_1") (pintype "passive"))
      (node (ref "U$1") (pin "2B") (pinfunction "2B_2B") (pintype "output"))
    )
    (net (code "101") (name "Net-(A-MOT1-Pad2)") (class "Default")
      (node (ref "A-MOT1") (pin "2") (pinfunction "2_2") (pintype "bidirectional"))
      (node (ref "A-MOT2") (pin "2") (pinfunction "2_2") (pintype "passive"))
      (node (ref "U$1") (pin "2A") (pinfunction "2A_2A") (pintype "output"))
    )
    (net (code "102") (name "Net-(A-MOT1-Pad3)") (class "Default")
      (node (ref "A-MOT1") (pin "3") (pinfunction "3_3") (pintype "bidirectional"))
      (node (ref "A-MOT2") (pin "3") (pinfunction "3_3") (pintype "passive"))
      (node (ref "U$1") (pin "1A") (pinfunction "1A_1A") (pintype "output"))
    )
    (net (code "103") (name "Net-(A-MOT1-Pad4)") (class "Default")
      (node (ref "A-MOT1") (pin "4") (pinfunction "4_4") (pintype "bidirectional"))
      (node (ref "A-MOT2") (pin "4") (pinfunction "4_4") (pintype "passive"))
      (node (ref "U$1") (pin "1B") (pinfunction "1B_1B") (pintype "output"))
    )
    (net (code "104") (name "Net-(A_STP-PadA)") (class "Default")
      (node (ref "A_STP") (pin "A") (pinfunction "A_A") (pintype "passive"))
      (node (ref "R6") (pin "1") (pinfunction "1_1") (pintype "passive"))
    )
    (net (code "105") (name "Net-(B-MOT1-Pad1)") (class "Default")
      (node (ref "B-MOT1") (pin "1") (pinfunction "1_1") (pintype "bidirectional"))
      (node (ref "B-MOT2") (pin "1") (pinfunction "1_1") (pintype "passive"))
      (node (ref "U$7") (pin "2B") (pinfunction "2B_2B") (pintype "output"))
    )
    (net (code "106") (name "Net-(B-MOT1-Pad2)") (class "Default")
      (node (ref "B-MOT1") (pin "2") (pinfunction "2_2") (pintype "bidirectional"))
      (node (ref "B-MOT2") (pin "2") (pinfunction "2_2") (pintype "passive"))
      (node (ref "U$7") (pin "2A") (pinfunction "2A_2A") (pintype "output"))
    )
    (net (code "107") (name "Net-(B-MOT1-Pad3)") (class "Default")
      (node (ref "B-MOT1") (pin "3") (pinfunction "3_3") (pintype "bidirectional"))
      (node (ref "B-MOT2") (pin "3") (pinfunction "3_3") (pintype "passive"))
      (node (ref "U$7") (pin "1A") (pinfunction "1A_1A") (pintype "output"))
    )
    (net (code "108") (name "Net-(B-MOT1-Pad4)") (class "Default")
      (node (ref "B-MOT1") (pin "4") (pinfunction "4_4") (pintype "bidirectional"))
      (node (ref "B-MOT2") (pin "4") (pinfunction "4_4") (pintype "passive"))
      (node (ref "U$7") (pin "1B") (pinfunction "1B_1B") (pintype "output"))
    )
    (net (code "109") (name "Net-(B_STP-PadA)") (class "Default")
      (node (ref "B_STP") (pin "A") (pinfunction "A_A") (pintype "passive"))
      (node (ref "R11") (pin "1") (pinfunction "1_1") (pintype "passive"))
    )
    (net (code "110") (name "Net-(C-MOT1-Pad1)") (class "Default")
      (node (ref "C-MOT1") (pin "1") (pinfunction "1_1") (pintype "bidirectional"))
      (node (ref "C-MOT2") (pin "1") (pinfunction "1_1") (pintype "passive"))
      (node (ref "U$6") (pin "2B") (pinfunction "2B_2B") (pintype "output"))
    )
    (net (code "111") (name "Net-(C-MOT1-Pad2)") (class "Default")
      (node (ref "C-MOT1") (pin "2") (pinfunction "2_2") (pintype "bidirectional"))
      (node (ref "C-MOT2") (pin "2") (pinfunction "2_2") (pintype "passive"))
      (node (ref "U$6") (pin "2A") (pinfunction "2A_2A") (pintype "output"))
    )
    (net (code "112") (name "Net-(C-MOT1-Pad3)") (class "Default")
      (node (ref "C-MOT1") (pin "3") (pinfunction "3_3") (pintype "bidirectional"))
      (node (ref "C-MOT2") (pin "3") (pinfunction "3_3") (pintype "passive"))
      (node (ref "U$6") (pin "1A") (pinfunction "1A_1A") (pintype "output"))
    )
    (net (code "113") (name "Net-(C-MOT1-Pad4)") (class "Default")
      (node (ref "C-MOT1") (pin "4") (pinfunction "4_4") (pintype "bidirectional"))
      (node (ref "C-MOT2") (pin "4") (pinfunction "4_4") (pintype "passive"))
      (node (ref "U$6") (pin "1B") (pinfunction "1B_1B") (pintype "output"))
    )
    (net (code "114") (name "Net-(C5-Pad1)") (class "Default")
      (node (ref "C5") (pin "1") (pinfunction "1_1") (pintype "passive"))
      (node (ref "IC1") (pin "COMP") (pinfunction "COMP_COMP") (pintype "bidirectional"))
    )
    (net (code "115") (name "Net-(C5-Pad2)") (class "Default")
      (node (ref "C5") (pin "2") (pinfunction "2_2") (pintype "passive"))
      (node (ref "R7") (pin "2") (pinfunction "2_2") (pintype "passive"))
    )
    (net (code "116") (name "Net-(C8-Pad1)") (class "Default")
      (node (ref "C8") (pin "1") (pinfunction "1_1") (pintype "passive"))
      (node (ref "IC1") (pin "BS") (pinfunction "BS_BS") (pintype "bidirectional"))
    )
    (net (code "117") (name "Net-(C8-Pad2)") (class "Default")
      (node (ref "C8") (pin "2") (pinfunction "2_2") (pintype "passive"))
      (node (ref "D1") (pin "A") (pinfunction "A_A") (pintype "passive"))
      (node (ref "IC1") (pin "SW") (pinfunction "SW_SW") (pintype "bidirectional"))
      (node (ref "L1") (pin "1") (pinfunction "1_1") (pintype "passive"))
    )
    (net (code "118") (name "Net-(C9-Pad1)") (class "Default")
      (node (ref "C9") (pin "1") (pinfunction "1_1") (pintype "passive"))
      (node (ref "IC1") (pin "SS") (pinfunction "SS_SS") (pintype "bidirectional"))
    )
    (net (code "119") (name "Net-(C12-Pad+)") (class "Default")
      (node (ref "C12") (pin "+") (pinfunction "+_+") (pintype "passive"))
      (node (ref "C7") (pin "1") (pinfunction "1_1") (pintype "passive"))
      (node (ref "L1") (pin "2") (pinfunction "2_2") (pintype "passive"))
      (node (ref "ON_BOARD_PWR") (pin "2") (pinfunction "2_2") (pintype "passive"))
      (node (ref "R12") (pin "1") (pinfunction "1_1") (pintype "passive"))
      (node (ref "R9") (pin "2") (pinfunction "2_2") (pintype "passive"))
    )
    (net (code "120") (name "Net-(C_STP-PadA)") (class "Default")
      (node (ref "C_STP") (pin "A") (pinfunction "A_A") (pintype "passive"))
      (node (ref "R3") (pin "1") (pinfunction "1_1") (pintype "passive"))
    )
    (net (code "121") (name "Net-(D2-PadA)") (class "Default")
      (node (ref "D2") (pin "A") (pinfunction "A_A") (pintype "passive"))
      (node (ref "ON_BOARD_PWR") (pin "1") (pinfunction "1_1") (pintype "passive"))
    )
    (net (code "122") (name "Net-(D13-PadA)") (class "Default")
      (node (ref "D13") (pin "A") (pinfunction "A_A") (pintype "passive"))
      (node (ref "RN1") (pin "1") (pinfunction "1_1") (pintype "passive"))
    )
    (net (code "123") (name "Net-(IC1-PadEN)") (class "Default")
      (node (ref "IC1") (pin "EN") (pinfunction "EN_EN") (pintype "bidirectional"))
      (node (ref "R4") (pin "2") (pinfunction "2_2") (pintype "passive"))
    )
    (net (code "124") (name "Net-(IC1-PadFB)") (class "Default")
      (node (ref "IC1") (pin "FB") (pinfunction "FB_FB") (pintype "bidirectional"))
      (node (ref "R10") (pin "2") (pinfunction "2_2") (pintype "passive"))
      (node (ref "R9") (pin "1") (pinfunction "1_1") (pintype "passive"))
    )
    (net (code "125") (name "Net-(PWR1-PadA)") (class "Default")
      (node (ref "PWR1") (pin "A") (pinfunction "A_A") (pintype "passive"))
      (node (ref "R12") (pin "2") (pinfunction "2_2") (pintype "passive"))
    )
    (net (code "126") (name "Net-(R1-Pad1)") (class "Default")
      (node (ref "R1") (pin "1") (pinfunction "1_1") (pintype "passive"))
      (node (ref "SJ7") (pin "2") (pinfunction "2_2") (pintype "passive"))
      (node (ref "U$1") (pin "MS1") (pinfunction "MS1_MS1") (pintype "input"))
    )
    (net (code "127") (name "Net-(R5-Pad1)") (class "Default")
      (node (ref "R5") (pin "1") (pinfunction "1_1") (pintype "passive"))
      (node (ref "SJ1") (pin "2") (pinfunction "2_2") (pintype "passive"))
      (node (ref "U$6") (pin "MS1") (pinfunction "MS1_MS1") (pintype "input"))
    )
    (net (code "128") (name "Net-(R8-Pad1)") (class "Default")
      (node (ref "R8") (pin "1") (pinfunction "1_1") (pintype "passive"))
      (node (ref "SJ3") (pin "2") (pinfunction "2_2") (pintype "passive"))
      (node (ref "U$7") (pin "MS1") (pinfunction "MS1_MS1") (pintype "input"))
    )
    (net (code "129") (name "Net-(RN1B-1)") (class "Default")
      (node (ref "RN1") (pin "2") (pinfunction "1_2") (pintype "passive"))
      (node (ref "RX_LED") (pin "C") (pinfunction "C_C") (pintype "passive"))
    )
    (net (code "130") (name "Net-(RN1C-1)") (class "Default")
      (node (ref "RN1") (pin "3") (pinfunction "1_3") (pintype "passive"))
      (node (ref "TX_LED") (pin "C") (pinfunction "C_C") (pintype "passive"))
    )
    (net (code "131") (name "Net-(RN1D-1)") (class "Default")
      (node (ref "PWR") (pin "A") (pinfunction "A_A") (pintype "passive"))
      (node (ref "RN1") (pin "4") (pinfunction "1_4") (pintype "passive"))
    )
    (net (code "132") (name "Net-(SJ2-Pad2)") (class "Default")
      (node (ref "SJ2") (pin "2") (pinfunction "2_2") (pintype "passive"))
      (node (ref "U$6") (pin "MS2") (pinfunction "MS2_MS2") (pintype "input"))
    )
    (net (code "133") (name "Net-(SJ4-Pad2)") (class "Default")
      (node (ref "SJ4") (pin "2") (pinfunction "2_2") (pintype "passive"))
      (node (ref "U$7") (pin "MS2") (pinfunction "MS2_MS2") (pintype "input"))
    )
    (net (code "134") (name "Net-(SJ5-Pad2)") (class "Default")
      (node (ref "SJ5") (pin "2") (pinfunction "2_2") (pintype "passive"))
      (node (ref "U$6") (pin "MS3") (pinfunction "MS3_MS3") (pintype "input"))
    )
    (net (code "135") (name "Net-(SJ6-Pad2)") (class "Default")
      (node (ref "SJ6") (pin "2") (pinfunction "2_2") (pintype "passive"))
      (node (ref "U$7") (pin "MS3") (pinfunction "MS3_MS3") (pintype "input"))
    )
    (net (code "136") (name "Net-(SJ8-Pad2)") (class "Default")
      (node (ref "SJ8") (pin "2") (pinfunction "2_2") (pintype "passive"))
      (node (ref "U$1") (pin "MS2") (pinfunction "MS2_MS2") (pintype "input"))
    )
    (net (code "137") (name "Net-(SJ9-Pad2)") (class "Default")
      (node (ref "SJ9") (pin "2") (pinfunction "2_2") (pintype "passive"))
      (node (ref "U$1") (pin "MS3") (pinfunction "MS3_MS3") (pintype "input"))
    )
    (net (code "138") (name "Net-(U$1-SLEEP)") (class "Default")
      (node (ref "U$1") (pin "RST") (pinfunction "RST_RST") (pintype "input"))
      (node (ref "U$1") (pin "SLP") (pinfunction "SLEEP_SLP") (pintype "input"))
    )
    (net (code "139") (name "Net-(U$6-SLEEP)") (class "Default")
      (node (ref "U$6") (pin "RST") (pinfunction "RST_RST") (pintype "input"))
      (node (ref "U$6") (pin "SLP") (pinfunction "SLEEP_SLP") (pintype "input"))
    )
    (net (code "140") (name "Net-(U$7-SLEEP)") (class "Default")
      (node (ref "U$7") (pin "RST") (pinfunction "RST_RST") (pintype "input"))
      (node (ref "U$7") (pin "SLP") (pinfunction "SLEEP_SLP") (pintype "input"))
    )
    (net (code "141") (name "VCC") (class "Default")
      (node (ref "D2") (pin "C") (pinfunction "C_C") (pintype "passive"))
      (node (ref "IC5") (pin "20") (pinfunction "VCC_20") (pintype "power_in"))
      (node (ref "JP15") (pin "5") (pinfunction "5_5") (pintype "passive"))
      (node (ref "R18") (pin "1") (pinfunction "1_1") (pintype "passive"))
      (node (ref "R19") (pin "1") (pinfunction "1_1") (pintype "passive"))
      (node (ref "R2") (pin "1") (pinfunction "1_1") (pintype "passive"))
      (node (ref "RN1") (pin "5") (pinfunction "2_5") (pintype "passive"))
      (node (ref "RX_LED") (pin "A") (pinfunction "A_A") (pintype "passive"))
      (node (ref "SER1") (pin "2") (pinfunction "2_2") (pintype "passive"))
      (node (ref "SER2") (pin "2") (pinfunction "2_2") (pintype "passive"))
      (node (ref "SJ1") (pin "1") (pinfunction "1_1") (pintype "passive"))
      (node (ref "SJ2") (pin "1") (pinfunction "1_1") (pintype "passive"))
      (node (ref "SJ3") (pin "1") (pinfunction "1_1") (pintype "passive"))
      (node (ref "SJ4") (pin "1") (pinfunction "1_1") (pintype "passive"))
      (node (ref "SJ5") (pin "1") (pinfunction "1_1") (pintype "passive"))
      (node (ref "SJ6") (pin "1") (pinfunction "1_1") (pintype "passive"))
      (node (ref "SJ7") (pin "1") (pinfunction "1_1") (pintype "passive"))
      (node (ref "SJ8") (pin "1") (pinfunction "1_1") (pintype "passive"))
      (node (ref "SJ9") (pin "1") (pinfunction "1_1") (pintype "passive"))
      (node (ref "TFT") (pin "3") (pinfunction "3_3") (pintype "passive"))
      (node (ref "TX_LED") (pin "A") (pinfunction "A_A") (pintype "passive"))
      (node (ref "U$1") (pin "VDD") (pinfunction "VDD_VDD") (pintype "power_in"))
      (node (ref "U$6") (pin "VDD") (pinfunction "VDD_VDD") (pintype "power_in"))
      (node (ref "U$7") (pin "VDD") (pinfunction "VDD_VDD") (pintype "power_in"))
      (node (ref "U1") (pin "5V@0") (pinfunction "5V_5V@0") (pintype "power_in"))
      (node (ref "U1") (pin "5V@1") (pinfunction "5V_5V@1") (pintype "power_in"))
      (node (ref "U1") (pin "5V@2") (pinfunction "5V_5V@2") (pintype "power_in"))
    )
    (net (code "142") (name "unconnected-(IC3A-Y3-Pad16)") (class "Default")
      (node (ref "IC3") (pin "16") (pinfunction "Y3_16") (pintype "tri_state"))
    )
    (net (code "143") (name "unconnected-(IC3A-Y4-Pad15)") (class "Default")
      (node (ref "IC3") (pin "15") (pinfunction "Y4_15") (pintype "tri_state"))
    )
    (net (code "144") (name "unconnected-(IC3A-Y5-Pad14)") (class "Default")
      (node (ref "IC3") (pin "14") (pinfunction "Y5_14") (pintype "tri_state"))
    )
    (net (code "145") (name "unconnected-(IC3A-Y6-Pad13)") (class "Default")
      (node (ref "IC3") (pin "13") (pinfunction "Y6_13") (pintype "tri_state"))
    )
    (net (code "146") (name "unconnected-(IC3A-Y8-Pad11)") (class "Default")
      (node (ref "IC3") (pin "11") (pinfunction "Y8_11") (pintype "tri_state"))
    )
    (net (code "147") (name "unconnected-(IC4A-Y8-Pad11)") (class "Default")
      (node (ref "IC4") (pin "11") (pinfunction "Y8_11") (pintype "tri_state"))
    )
    (net (code "148") (name "unconnected-(IC5A-Y1-Pad18)") (class "Default")
      (node (ref "IC5") (pin "18") (pinfunction "Y1_18") (pintype "tri_state"))
    )
    (net (code "149") (name "unconnected-(IC5A-Y5-Pad14)") (class "Default")
      (node (ref "IC5") (pin "14") (pinfunction "Y5_14") (pintype "tri_state"))
    )
    (net (code "150") (name "unconnected-(IC5A-Y6-Pad13)") (class "Default")
      (node (ref "IC5") (pin "13") (pinfunction "Y6_13") (pintype "tri_state"))
    )
    (net (code "151") (name "unconnected-(IC5A-Y7-Pad12)") (class "Default")
      (node (ref "IC5") (pin "12") (pinfunction "Y7_12") (pintype "tri_state"))
    )
    (net (code "152") (name "unconnected-(IC5A-Y8-Pad11)") (class "Default")
      (node (ref "IC5") (pin "11") (pinfunction "Y8_11") (pintype "tri_state"))
    )
    (net (code "153") (name "unconnected-(TFT-Pad5)") (class "Default")
      (node (ref "TFT") (pin "5") (pinfunction "5_5") (pintype "passive"))
    )
    (net (code "154") (name "unconnected-(TFT-Pad24)") (class "Default")
      (node (ref "TFT") (pin "24") (pinfunction "24_24") (pintype "passive"))
    )
    (net (code "155") (name "unconnected-(TFT-Pad31)") (class "Default")
      (node (ref "TFT") (pin "31") (pinfunction "31_31") (pintype "passive"))
    )
    (net (code "156") (name "unconnected-(TFT-Pad35)") (class "Default")
      (node (ref "TFT") (pin "35") (pinfunction "35_35") (pintype "passive"))
    )
    (net (code "157") (name "unconnected-(TFT-Pad38)") (class "Default")
      (node (ref "TFT") (pin "38") (pinfunction "38_38") (pintype "passive"))
    )
    (net (code "158") (name "unconnected-(TFT-Pad39)") (class "Default")
      (node (ref "TFT") (pin "39") (pinfunction "39_39") (pintype "passive"))
    )
    (net (code "159") (name "unconnected-(TFT-Pad40)") (class "Default")
      (node (ref "TFT") (pin "40") (pinfunction "40_40") (pintype "passive"))
    )
  )
)
